# BNO055.net
KiCad netlist of a schematic drawn in Altium Designer
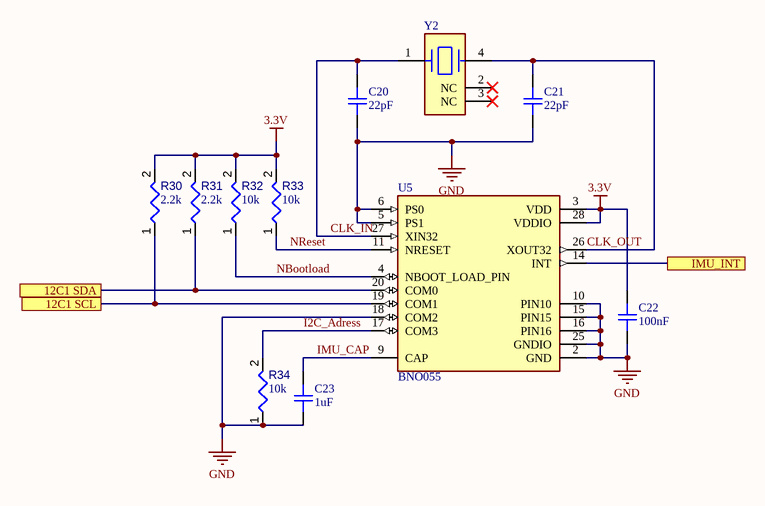
[diagram p0: BNO055.SchDoc]

(export (version "E")
  (design (tool "Eeschema 10.0.6"))
  (components
    (comp (ref "C20")
      (value "22pF")
      (footprint "CAP_0603")
      (description "Capacitor SMD 0603")
      (libsource (lib "Schematic-Lib-PhilsLab") (part "CAP_0603"))
    )
    (comp (ref "C21")
      (value "22pF")
      (footprint "CAP_0603")
      (description "Capacitor SMD 0603")
      (libsource (lib "Schematic-Lib-PhilsLab") (part "CAP_0603"))
    )
    (comp (ref "C22")
      (value "100nF")
      (footprint "CAP_0603")
      (description "Capacitor SMD 0603")
      (libsource (lib "Schematic-Lib-PhilsLab") (part "CAP_0603"))
    )
    (comp (ref "C23")
      (value "1uF")
      (footprint "CAP_0603")
      (description "Capacitor SMD 0603")
      (libsource (lib "Schematic-Lib-PhilsLab") (part "CAP_0603"))
    )
    (comp (ref "R30")
      (value "2.2k")
      (footprint "RESC0402(1005)_L")
      (description "324K 0.063W 1% 0402 (1005 Metric)  SMD")
      (fields (field (name "TOLERANCE") "1%") (field (name "POWER") "63mW"))
      (libsource (lib "Edgar Restor") (part "324KR2F"))
    )
    (comp (ref "R31")
      (value "2.2k")
      (footprint "RESC0402(1005)_L")
      (description "324K 0.063W 1% 0402 (1005 Metric)  SMD")
      (fields (field (name "TOLERANCE") "1%") (field (name "POWER") "63mW"))
      (libsource (lib "Edgar Restor") (part "324KR2F"))
    )
    (comp (ref "R32")
      (value "10k")
      (footprint "RESC0402(1005)_L")
      (description "324K 0.063W 1% 0402 (1005 Metric)  SMD")
      (fields (field (name "TOLERANCE") "1%") (field (name "POWER") "63mW"))
      (libsource (lib "Edgar Restor") (part "324KR2F"))
    )
    (comp (ref "R33")
      (value "10k")
      (footprint "RESC0402(1005)_L")
      (description "324K 0.063W 1% 0402 (1005 Metric)  SMD")
      (fields (field (name "TOLERANCE") "1%") (field (name "POWER") "63mW"))
      (libsource (lib "Edgar Restor") (part "324KR2F"))
    )
    (comp (ref "R34")
      (value "10k")
      (footprint "RESC0402(1005)_L")
      (description "324K 0.063W 1% 0402 (1005 Metric)  SMD")
      (fields (field (name "TOLERANCE") "1%") (field (name "POWER") "63mW"))
      (libsource (lib "Edgar Restor") (part "324KR2F"))
    )
    (comp (ref "U5")
      (value "BNO055")
      (footprint "LGA28R50P4X10_380X520X100")
      (description "BNO055 9-axis Absolute Orientation Sensor ( SiP ) w/Sensors and Sensor Fusion")
      (libsource (lib "BNO055") (part "BNO055"))
    )
    (comp (ref "Y2")
      (value "ABS25-32.768KHZ-T")
      (footprint "FP-ABS25-MFG")
      (description "CRYSTAL 32.7680KHZ 12.5PF SMD")
      (fields (field (name "TOLERANCE") "20ppm"))
      (libsource (lib "Altium Content Vault") (part "d2378e42ab3755ffcd472789242ec61"))
    )
  )
  (nets
    (net (code "1") (name "/12C1 SCL") (class "Default")
      (node (ref "R30") (pin "1") (pinfunction "1_1") (pintype "passive"))
      (node (ref "U5") (pin "19") (pinfunction "COM1_19") (pintype "bidirectional"))
    )
    (net (code "2") (name "/12C1 SDA") (class "Default")
      (node (ref "R31") (pin "1") (pinfunction "1_1") (pintype "passive"))
      (node (ref "U5") (pin "20") (pinfunction "COM0_20") (pintype "bidirectional"))
    )
    (net (code "3") (name "/CLK_IN") (class "Default")
      (node (ref "C20") (pin "2") (pinfunction "2_2") (pintype "passive"))
      (node (ref "U5") (pin "27") (pinfunction "XIN32_27") (pintype "input"))
      (node (ref "Y2") (pin "1") (pinfunction "1_1") (pintype "passive"))
    )
    (net (code "4") (name "/CLK_OUT") (class "Default")
      (node (ref "C21") (pin "2") (pinfunction "2_2") (pintype "passive"))
      (node (ref "U5") (pin "26") (pinfunction "XOUT32_26") (pintype "output"))
      (node (ref "Y2") (pin "4") (pinfunction "4_4") (pintype "passive"))
    )
    (net (code "5") (name "/I2C_Adress") (class "Default")
      (node (ref "R34") (pin "2") (pinfunction "2_2") (pintype "passive"))
      (node (ref "U5") (pin "17") (pinfunction "COM3_17") (pintype "bidirectional"))
    )
    (net (code "6") (name "/IMU_CAP") (class "Default")
      (node (ref "C23") (pin "2") (pinfunction "2_2") (pintype "passive"))
      (node (ref "U5") (pin "9") (pinfunction "CAP_9") (pintype "passive"))
    )
    (net (code "7") (name "/IMU_INT") (class "Default")
      (node (ref "U5") (pin "14") (pinfunction "INT_14") (pintype "output"))
    )
    (net (code "8") (name "/NBootload") (class "Default")
      (node (ref "R32") (pin "1") (pinfunction "1_1") (pintype "passive"))
      (node (ref "U5") (pin "4") (pinfunction "NBOOT_LOAD_PIN_4") (pintype "bidirectional"))
    )
    (net (code "9") (name "/NReset") (class "Default")
      (node (ref "R33") (pin "1") (pinfunction "1_1") (pintype "passive"))
      (node (ref "U5") (pin "11") (pinfunction "NRESET_11") (pintype "input"))
    )
    (net (code "10") (name "3.3V") (class "Default")
      (node (ref "C22") (pin "2") (pinfunction "2_2") (pintype "passive"))
      (node (ref "R30") (pin "2") (pinfunction "2_2") (pintype "passive"))
      (node (ref "R31") (pin "2") (pinfunction "2_2") (pintype "passive"))
      (node (ref "R32") (pin "2") (pinfunction "2_2") (pintype "passive"))
      (node (ref "R33") (pin "2") (pinfunction "2_2") (pintype "passive"))
      (node (ref "U5") (pin "28") (pinfunction "VDDIO_28") (pintype "power_in"))
      (node (ref "U5") (pin "3") (pinfunction "VDD_3") (pintype "power_in"))
    )
    (net (code "11") (name "GND") (class "Default")
      (node (ref "C20") (pin "1") (pinfunction "1_1") (pintype "passive"))
      (node (ref "C21") (pin "1") (pinfunction "1_1") (pintype "passive"))
      (node (ref "C22") (pin "1") (pinfunction "1_1") (pintype "passive"))
      (node (ref "C23") (pin "1") (pinfunction "1_1") (pintype "passive"))
      (node (ref "R34") (pin "1") (pinfunction "1_1") (pintype "passive"))
      (node (ref "U5") (pin "10") (pinfunction "PIN10_10") (pintype "power_in"))
      (node (ref "U5") (pin "15") (pinfunction "PIN15_15") (pintype "power_in"))
      (node (ref "U5") (pin "16") (pinfunction "PIN16_16") (pintype "power_in"))
      (node (ref "U5") (pin "18") (pinfunction "COM2_18") (pintype "bidirectional"))
      (node (ref "U5") (pin "2") (pinfunction "GND_2") (pintype "power_in"))
      (node (ref "U5") (pin "25") (pinfunction "GNDIO_25") (pintype "power_in"))
      (node (ref "U5") (pin "5") (pinfunction "PS1_5") (pintype "input"))
      (node (ref "U5") (pin "6") (pinfunction "PS0_6") (pintype "input"))
    )
    (net (code "12") (name "unconnected-(Y2-NC-Pad2)") (class "Default")
      (node (ref "Y2") (pin "2") (pinfunction "NC_2") (pintype "passive+no_connect"))
    )
    (net (code "13") (name "unconnected-(Y2-NC-Pad3)") (class "Default")
      (node (ref "Y2") (pin "3") (pinfunction "NC_3") (pintype "passive+no_connect"))
    )
  )
)
